# MySXMotion.net
KiCad netlist of a schematic drawn in EAGLE
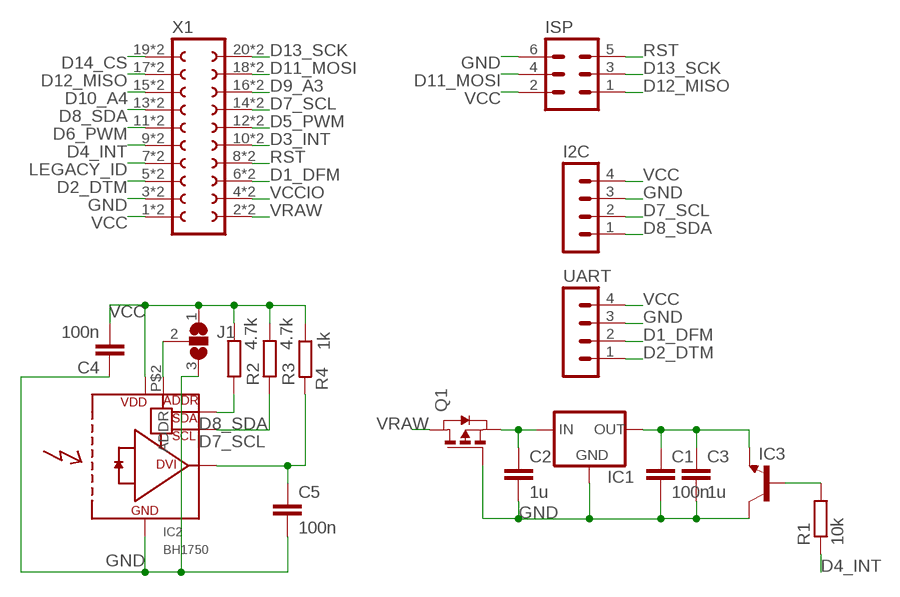
[diagram p0: schematic, sheet 1]

(export (version "E")
  (design (tool "Eeschema 10.0.6"))
  (components
    (comp (ref "C1")
      (value "100n")
      (footprint "eagle-import:C0603")
      (libsource (lib "eagle-import") (part "C-EUC0603"))
    )
    (comp (ref "C2")
      (value "1u")
      (footprint "eagle-import:C0603")
      (libsource (lib "eagle-import") (part "C-EUC0603"))
    )
    (comp (ref "C3")
      (value "1u")
      (footprint "eagle-import:C0805")
      (libsource (lib "eagle-import") (part "C-EUC0805"))
    )
    (comp (ref "C4")
      (value "100n")
      (footprint "eagle-import:C0603")
      (libsource (lib "eagle-import") (part "C-EUC0603"))
    )
    (comp (ref "C5")
      (value "100n")
      (footprint "eagle-import:C0603")
      (libsource (lib "eagle-import") (part "C-EUC0603"))
    )
    (comp (ref "I2C")
      (value "MA04-1")
      (footprint "eagle-import:MA04-1")
      (libsource (lib "eagle-import") (part "MA04-1"))
    )
    (comp (ref "IC1")
      (value "XC63FPM")
      (footprint "eagle-import:SOT23")
      (libsource (lib "eagle-import") (part "XC63FPM"))
    )
    (comp (ref "IC2")
      (value "BH1750")
      (footprint "eagle-import:WSOF6")
      (libsource (lib "eagle-import") (part "BH1750"))
    )
    (comp (ref "IC3")
      (value "-NPN-TO5")
      (footprint "eagle-import:TO5")
      (libsource (lib "eagle-import") (part "-NPN-TO5"))
    )
    (comp (ref "ISP")
      (value "MA03-2")
      (footprint "eagle-import:MA03-2")
      (libsource (lib "eagle-import") (part "MA03-2"))
    )
    (comp (ref "J1")
      (value "SJ2W")
      (footprint "eagle-import:SJ_2")
      (libsource (lib "eagle-import") (part "SJ2W"))
    )
    (comp (ref "Q1")
      (value "PMOSSOT23")
      (footprint "eagle-import:SOT-23")
      (libsource (lib "eagle-import") (part "PMOSSOT23"))
    )
    (comp (ref "R1")
      (value "10k")
      (footprint "eagle-import:R0603")
      (libsource (lib "eagle-import") (part "R-EU_R0603"))
    )
    (comp (ref "R2")
      (value "4.7k")
      (footprint "eagle-import:R0603")
      (libsource (lib "eagle-import") (part "R-EU_R0603"))
    )
    (comp (ref "R3")
      (value "4.7k")
      (footprint "eagle-import:R0603")
      (libsource (lib "eagle-import") (part "R-EU_R0603"))
    )
    (comp (ref "R4")
      (value "1k")
      (footprint "eagle-import:R0603")
      (libsource (lib "eagle-import") (part "R-EU_R0603"))
    )
    (comp (ref "UART")
      (value "MA04-1")
      (footprint "eagle-import:MA04-1")
      (libsource (lib "eagle-import") (part "MA04-1"))
    )
    (comp (ref "X1")
      (value "FE10-2")
      (footprint "eagle-import:FE10-2")
      (libsource (lib "eagle-import") (part "FE10-2"))
    )
  )
  (nets
    (net (code "1") (name "/D1_DFM") (class "Default")
      (node (ref "UART") (pin "2") (pinfunction "2_2") (pintype "passive"))
      (node (ref "X1") (pin "6") (pinfunction "6_6") (pintype "passive"))
      (node (ref "X1") (pin "P$6") (pinfunction "6_P$6") (pintype "passive"))
    )
    (net (code "2") (name "/D2_DTM") (class "Default")
      (node (ref "UART") (pin "1") (pinfunction "1_1") (pintype "passive"))
      (node (ref "X1") (pin "5") (pinfunction "5_5") (pintype "passive"))
      (node (ref "X1") (pin "P$5") (pinfunction "5_P$5") (pintype "passive"))
    )
    (net (code "3") (name "/D3_INT") (class "Default")
      (node (ref "X1") (pin "10") (pinfunction "10_10") (pintype "passive"))
      (node (ref "X1") (pin "P$10") (pinfunction "10_P$10") (pintype "passive"))
    )
    (net (code "4") (name "/D4_INT") (class "Default")
      (node (ref "R1") (pin "1") (pinfunction "1_1") (pintype "passive"))
      (node (ref "X1") (pin "9") (pinfunction "9_9") (pintype "passive"))
      (node (ref "X1") (pin "P$9") (pinfunction "9_P$9") (pintype "passive"))
    )
    (net (code "5") (name "/D5_PWM") (class "Default")
      (node (ref "X1") (pin "12") (pinfunction "12_12") (pintype "passive"))
      (node (ref "X1") (pin "P$12") (pinfunction "12_P$12") (pintype "passive"))
    )
    (net (code "6") (name "/D6_PWM") (class "Default")
      (node (ref "X1") (pin "11") (pinfunction "11_11") (pintype "passive"))
      (node (ref "X1") (pin "P$11") (pinfunction "11_P$11") (pintype "passive"))
    )
    (net (code "7") (name "/D7_SCL") (class "Default")
      (node (ref "I2C") (pin "2") (pinfunction "2_2") (pintype "passive"))
      (node (ref "IC2") (pin "P$6") (pinfunction "SCL_P$6") (pintype "input"))
      (node (ref "R3") (pin "1") (pinfunction "1_1") (pintype "passive"))
      (node (ref "X1") (pin "14") (pinfunction "14_14") (pintype "passive"))
      (node (ref "X1") (pin "P$14") (pinfunction "14_P$14") (pintype "passive"))
    )
    (net (code "8") (name "/D8_SDA") (class "Default")
      (node (ref "I2C") (pin "1") (pinfunction "1_1") (pintype "passive"))
      (node (ref "IC2") (pin "P$4") (pinfunction "SDA_P$4") (pintype "bidirectional"))
      (node (ref "R2") (pin "1") (pinfunction "1_1") (pintype "passive"))
      (node (ref "X1") (pin "13") (pinfunction "13_13") (pintype "passive"))
      (node (ref "X1") (pin "P$13") (pinfunction "13_P$13") (pintype "passive"))
    )
    (net (code "9") (name "/D9_A3") (class "Default")
      (node (ref "X1") (pin "16") (pinfunction "16_16") (pintype "passive"))
      (node (ref "X1") (pin "P$16") (pinfunction "16_P$16") (pintype "passive"))
    )
    (net (code "10") (name "/D10_A4") (class "Default")
      (node (ref "X1") (pin "15") (pinfunction "15_15") (pintype "passive"))
      (node (ref "X1") (pin "P$15") (pinfunction "15_P$15") (pintype "passive"))
    )
    (net (code "11") (name "/D11_MOSI") (class "Default")
      (node (ref "ISP") (pin "4") (pinfunction "4_4") (pintype "passive"))
      (node (ref "X1") (pin "18") (pinfunction "18_18") (pintype "passive"))
      (node (ref "X1") (pin "P$18") (pinfunction "18_P$18") (pintype "passive"))
    )
    (net (code "12") (name "/D12_MISO") (class "Default")
      (node (ref "ISP") (pin "1") (pinfunction "1_1") (pintype "passive"))
      (node (ref "X1") (pin "17") (pinfunction "17_17") (pintype "passive"))
      (node (ref "X1") (pin "P$17") (pinfunction "17_P$17") (pintype "passive"))
    )
    (net (code "13") (name "/D13_SCK") (class "Default")
      (node (ref "ISP") (pin "3") (pinfunction "3_3") (pintype "passive"))
      (node (ref "X1") (pin "20") (pinfunction "20_20") (pintype "passive"))
      (node (ref "X1") (pin "P$20") (pinfunction "20_P$20") (pintype "passive"))
    )
    (net (code "14") (name "/D14_CS") (class "Default")
      (node (ref "X1") (pin "19") (pinfunction "19_19") (pintype "passive"))
      (node (ref "X1") (pin "P$19") (pinfunction "19_P$19") (pintype "passive"))
    )
    (net (code "15") (name "/GND") (class "Default")
      (node (ref "C1") (pin "2") (pinfunction "2_2") (pintype "passive"))
      (node (ref "C2") (pin "2") (pinfunction "2_2") (pintype "passive"))
      (node (ref "C3") (pin "2") (pinfunction "2_2") (pintype "passive"))
      (node (ref "C4") (pin "1") (pinfunction "1_1") (pintype "passive"))
      (node (ref "C5") (pin "2") (pinfunction "2_2") (pintype "passive"))
      (node (ref "I2C") (pin "3") (pinfunction "3_3") (pintype "passive"))
      (node (ref "IC1") (pin "1") (pinfunction "GND_1") (pintype "input"))
      (node (ref "IC2") (pin "P$3") (pinfunction "GND_P$3") (pintype "power_in"))
      (node (ref "IC3") (pin "3") (pinfunction "C_3") (pintype "passive"))
      (node (ref "ISP") (pin "6") (pinfunction "6_6") (pintype "passive"))
      (node (ref "J1") (pin "3") (pinfunction "3_3") (pintype "passive"))
      (node (ref "Q1") (pin "3") (pinfunction "G_3") (pintype "passive"))
      (node (ref "UART") (pin "3") (pinfunction "3_3") (pintype "passive"))
      (node (ref "X1") (pin "3") (pinfunction "3_3") (pintype "passive"))
      (node (ref "X1") (pin "P$3") (pinfunction "3_P$3") (pintype "passive"))
    )
    (net (code "16") (name "/LEGACY_ID") (class "Default")
      (node (ref "X1") (pin "7") (pinfunction "7_7") (pintype "passive"))
      (node (ref "X1") (pin "P$7") (pinfunction "7_P$7") (pintype "passive"))
    )
    (net (code "17") (name "/RST") (class "Default")
      (node (ref "ISP") (pin "5") (pinfunction "5_5") (pintype "passive"))
      (node (ref "X1") (pin "8") (pinfunction "8_8") (pintype "passive"))
      (node (ref "X1") (pin "P$8") (pinfunction "8_P$8") (pintype "passive"))
    )
    (net (code "18") (name "/VCC") (class "Default")
      (node (ref "C4") (pin "2") (pinfunction "2_2") (pintype "passive"))
      (node (ref "I2C") (pin "4") (pinfunction "4_4") (pintype "passive"))
      (node (ref "IC2") (pin "P$1") (pinfunction "VCC_P$1") (pintype "power_in"))
      (node (ref "ISP") (pin "2") (pinfunction "2_2") (pintype "passive"))
      (node (ref "J1") (pin "1") (pinfunction "1_1") (pintype "passive"))
      (node (ref "R2") (pin "2") (pinfunction "2_2") (pintype "passive"))
      (node (ref "R3") (pin "2") (pinfunction "2_2") (pintype "passive"))
      (node (ref "R4") (pin "1") (pinfunction "1_1") (pintype "passive"))
      (node (ref "UART") (pin "4") (pinfunction "4_4") (pintype "passive"))
      (node (ref "X1") (pin "1") (pinfunction "1_1") (pintype "passive"))
      (node (ref "X1") (pin "P$1") (pinfunction "1_P$1") (pintype "passive"))
    )
    (net (code "19") (name "/VCCIO") (class "Default")
      (node (ref "X1") (pin "4") (pinfunction "4_4") (pintype "passive"))
      (node (ref "X1") (pin "P$4") (pinfunction "4_P$4") (pintype "passive"))
    )
    (net (code "20") (name "/VRAW") (class "Default")
      (node (ref "Q1") (pin "1") (pinfunction "D_1") (pintype "passive"))
      (node (ref "X1") (pin "2") (pinfunction "2_2") (pintype "passive"))
      (node (ref "X1") (pin "P$2") (pinfunction "2_P$2") (pintype "passive"))
    )
    (net (code "21") (name "Net-(IC1-IN)") (class "Default")
      (node (ref "C2") (pin "1") (pinfunction "1_1") (pintype "passive"))
      (node (ref "IC1") (pin "3") (pinfunction "IN_3") (pintype "input"))
      (node (ref "Q1") (pin "2") (pinfunction "S_2") (pintype "passive"))
    )
    (net (code "22") (name "Net-(IC1-OUT)") (class "Default")
      (node (ref "C1") (pin "1") (pinfunction "1_1") (pintype "passive"))
      (node (ref "C3") (pin "1") (pinfunction "1_1") (pintype "passive"))
      (node (ref "IC1") (pin "2") (pinfunction "OUT_2") (pintype "passive"))
      (node (ref "IC3") (pin "1") (pinfunction "E_1") (pintype "passive"))
    )
    (net (code "23") (name "Net-(IC2-ADDR)") (class "Default")
      (node (ref "IC2") (pin "P$2") (pinfunction "ADDR_P$2") (pintype "input"))
      (node (ref "J1") (pin "2") (pinfunction "2_2") (pintype "passive"))
    )
    (net (code "24") (name "Net-(IC2-DVI)") (class "Default")
      (node (ref "C5") (pin "1") (pinfunction "1_1") (pintype "passive"))
      (node (ref "IC2") (pin "P$5") (pinfunction "DVI_P$5") (pintype "output"))
      (node (ref "R4") (pin "2") (pinfunction "2_2") (pintype "passive"))
    )
    (net (code "25") (name "Net-(IC3-B)") (class "Default")
      (node (ref "IC3") (pin "2") (pinfunction "B_2") (pintype "passive"))
      (node (ref "R1") (pin "2") (pinfunction "2_2") (pintype "passive"))
    )
  )
)
